# wifi_ring.net
KiCad netlist of a schematic drawn in EAGLE
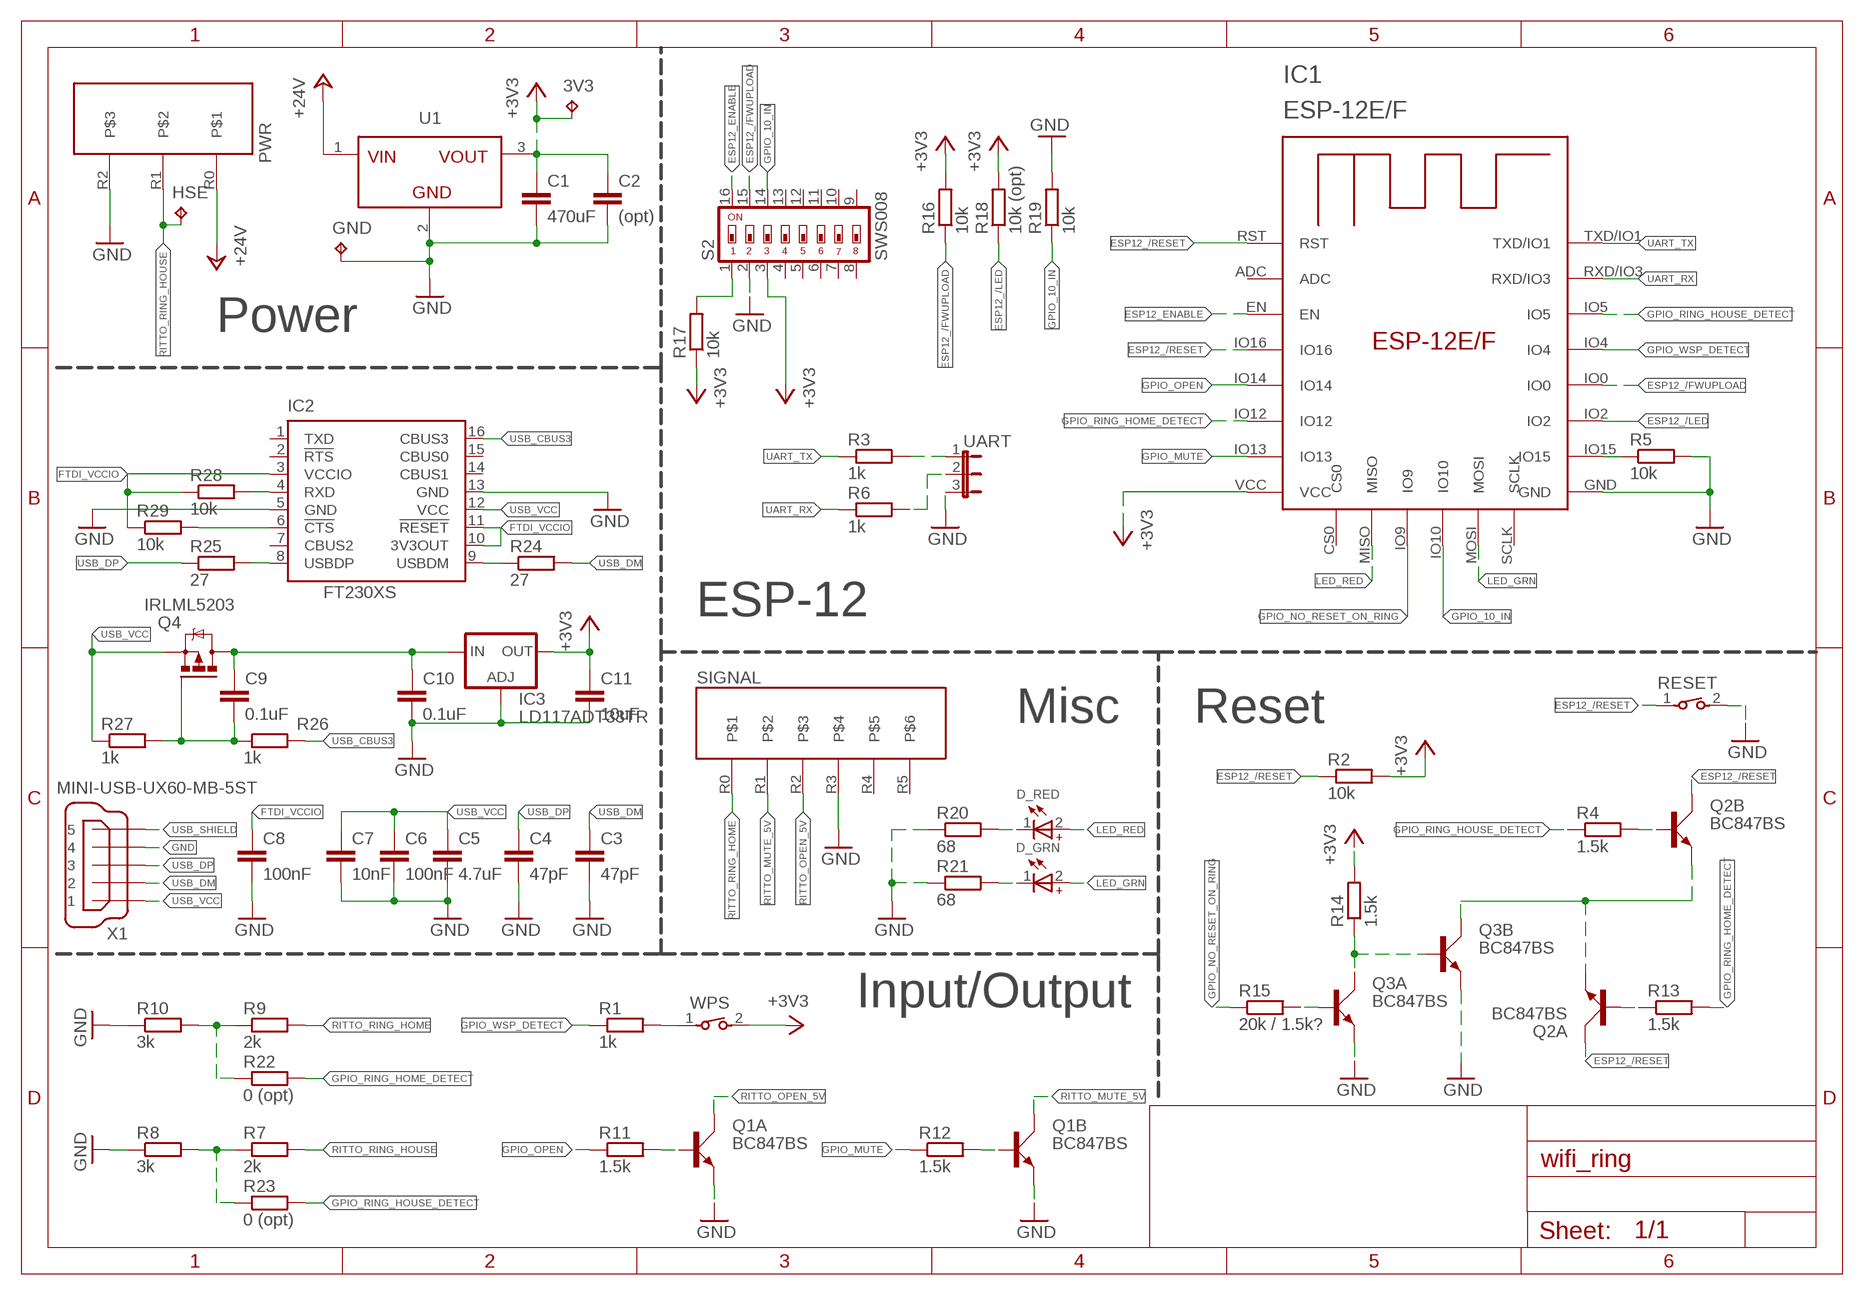
[diagram p0: schematic, sheet 1]

(export (version "E")
  (design (tool "Eeschema 10.0.6"))
  (components
    (comp (ref "3V3")
      (value "TPTP10SQ")
      (footprint "eagle-import:TP10SQ")
      (libsource (lib "eagle-import") (part "TPTP10SQ"))
    )
    (comp (ref "C1")
      (value "470uF")
      (footprint "eagle-import:C1206")
      (libsource (lib "eagle-import") (part "C-EUC1206"))
    )
    (comp (ref "C2")
      (value "(opt)")
      (footprint "eagle-import:C1206")
      (libsource (lib "eagle-import") (part "C-EUC1206"))
    )
    (comp (ref "C3")
      (value "47pF")
      (footprint "eagle-import:C1206")
      (libsource (lib "eagle-import") (part "C-EUC1206"))
    )
    (comp (ref "C4")
      (value "47pF")
      (footprint "eagle-import:C1206")
      (libsource (lib "eagle-import") (part "C-EUC1206"))
    )
    (comp (ref "C5")
      (value "4.7uF")
      (footprint "eagle-import:C1206")
      (libsource (lib "eagle-import") (part "C-EUC1206"))
    )
    (comp (ref "C6")
      (value "100nF")
      (footprint "eagle-import:C1206")
      (libsource (lib "eagle-import") (part "C-EUC1206"))
    )
    (comp (ref "C7")
      (value "10nF")
      (footprint "eagle-import:C1206")
      (libsource (lib "eagle-import") (part "C-EUC1206"))
    )
    (comp (ref "C8")
      (value "100nF")
      (footprint "eagle-import:C1206")
      (libsource (lib "eagle-import") (part "C-EUC1206"))
    )
    (comp (ref "C9")
      (value "0.1uF")
      (footprint "eagle-import:C1206")
      (libsource (lib "eagle-import") (part "C-EUC1206"))
    )
    (comp (ref "C10")
      (value "0.1uF")
      (footprint "eagle-import:C1206")
      (libsource (lib "eagle-import") (part "C-EUC1206"))
    )
    (comp (ref "C11")
      (value "10uF")
      (footprint "eagle-import:C1206")
      (libsource (lib "eagle-import") (part "C-EUC1206"))
    )
    (comp (ref "D_GRN")
      (value "WL-SMRW_1206_CYL_156120VS75300_NOR")
      (footprint "eagle-import:WL-SMRW_1206_CYL")
      (libsource (lib "eagle-import") (part "WL-SMRW_1206_CYL_NOR_156120VS75300"))
    )
    (comp (ref "D_RED")
      (value "WL-SMRW_1206_CYL_156120RS75300_NOR")
      (footprint "eagle-import:WL-SMRW_1206_CYL")
      (libsource (lib "eagle-import") (part "WL-SMRW_1206_CYL_NOR_156120RS75300"))
    )
    (comp (ref "GND")
      (value "TPTP10SQ")
      (footprint "eagle-import:TP10SQ")
      (libsource (lib "eagle-import") (part "TPTP10SQ"))
    )
    (comp (ref "HSE")
      (value "TPTP10SQ")
      (footprint "eagle-import:TP10SQ")
      (libsource (lib "eagle-import") (part "TPTP10SQ"))
    )
    (comp (ref "IC1")
      (value "ESP-12E/F")
      (footprint "eagle-import:ESP-12E")
      (libsource (lib "eagle-import") (part "ESP-12E/F"))
    )
    (comp (ref "IC2")
      (value "FT230XS")
      (footprint "eagle-import:SSOP16")
      (libsource (lib "eagle-import") (part "FT230XS"))
    )
    (comp (ref "IC3")
      (value "LD117ADT33TR")
      (footprint "eagle-import:DPACK")
      (libsource (lib "eagle-import") (part "LD117A?DT33TR"))
    )
    (comp (ref "PWR")
      (value "RAST_3")
      (footprint "eagle-import:RAST_3")
      (libsource (lib "eagle-import") (part "RAST_3"))
    )
    (comp (ref "Q1")
      (value "BC847BS")
      (footprint "eagle-import:SOT363_PHILIPS")
      (libsource (lib "eagle-import") (part "BC847BS"))
    )
    (comp (ref "Q2")
      (value "BC847BS")
      (footprint "eagle-import:SOT363_PHILIPS")
      (libsource (lib "eagle-import") (part "BC847BS"))
    )
    (comp (ref "Q3")
      (value "BC847BS")
      (footprint "eagle-import:SOT363_PHILIPS")
      (libsource (lib "eagle-import") (part "BC847BS"))
    )
    (comp (ref "Q4")
      (value "IRLML5203")
      (footprint "eagle-import:MICRO3")
      (libsource (lib "eagle-import") (part "IRLML5203"))
    )
    (comp (ref "R1")
      (value "1k")
      (footprint "eagle-import:R1206")
      (libsource (lib "eagle-import") (part "R-EU_R1206"))
    )
    (comp (ref "R2")
      (value "10k")
      (footprint "eagle-import:R1206")
      (libsource (lib "eagle-import") (part "R-EU_R1206"))
    )
    (comp (ref "R3")
      (value "1k")
      (footprint "eagle-import:R1206")
      (libsource (lib "eagle-import") (part "R-EU_R1206"))
    )
    (comp (ref "R4")
      (value "1.5k")
      (footprint "eagle-import:R1206")
      (libsource (lib "eagle-import") (part "R-EU_R1206"))
    )
    (comp (ref "R5")
      (value "10k")
      (footprint "eagle-import:R1206")
      (libsource (lib "eagle-import") (part "R-EU_R1206"))
    )
    (comp (ref "R6")
      (value "1k")
      (footprint "eagle-import:R1206")
      (libsource (lib "eagle-import") (part "R-EU_R1206"))
    )
    (comp (ref "R7")
      (value "2k")
      (footprint "eagle-import:R1206")
      (libsource (lib "eagle-import") (part "R-EU_R1206"))
    )
    (comp (ref "R8")
      (value "3k")
      (footprint "eagle-import:R1206")
      (libsource (lib "eagle-import") (part "R-EU_R1206"))
    )
    (comp (ref "R9")
      (value "2k")
      (footprint "eagle-import:R1206")
      (libsource (lib "eagle-import") (part "R-EU_R1206"))
    )
    (comp (ref "R10")
      (value "3k")
      (footprint "eagle-import:R1206")
      (libsource (lib "eagle-import") (part "R-EU_R1206"))
    )
    (comp (ref "R11")
      (value "1.5k")
      (footprint "eagle-import:R1206")
      (libsource (lib "eagle-import") (part "R-EU_R1206"))
    )
    (comp (ref "R12")
      (value "1.5k")
      (footprint "eagle-import:R1206")
      (libsource (lib "eagle-import") (part "R-EU_R1206"))
    )
    (comp (ref "R13")
      (value "1.5k")
      (footprint "eagle-import:R1206")
      (libsource (lib "eagle-import") (part "R-EU_R1206"))
    )
    (comp (ref "R14")
      (value "1.5k")
      (footprint "eagle-import:R1206")
      (libsource (lib "eagle-import") (part "R-EU_R1206"))
    )
    (comp (ref "R15")
      (value "20k / 1.5k?")
      (footprint "eagle-import:R1206")
      (libsource (lib "eagle-import") (part "R-EU_R1206"))
    )
    (comp (ref "R16")
      (value "10k")
      (footprint "eagle-import:R1206")
      (libsource (lib "eagle-import") (part "R-EU_R1206"))
    )
    (comp (ref "R17")
      (value "10k")
      (footprint "eagle-import:R1206")
      (libsource (lib "eagle-import") (part "R-EU_R1206"))
    )
    (comp (ref "R18")
      (value "10k (opt)")
      (footprint "eagle-import:R1206")
      (libsource (lib "eagle-import") (part "R-EU_R1206"))
    )
    (comp (ref "R19")
      (value "10k")
      (footprint "eagle-import:R1206")
      (libsource (lib "eagle-import") (part "R-EU_R1206"))
    )
    (comp (ref "R20")
      (value "68")
      (footprint "eagle-import:R1206")
      (libsource (lib "eagle-import") (part "R-EU_R1206"))
    )
    (comp (ref "R21")
      (value "68")
      (footprint "eagle-import:R1206")
      (libsource (lib "eagle-import") (part "R-EU_R1206"))
    )
    (comp (ref "R22")
      (value "0 (opt)")
      (footprint "eagle-import:R1206")
      (libsource (lib "eagle-import") (part "R-EU_R1206"))
    )
    (comp (ref "R23")
      (value "0 (opt)")
      (footprint "eagle-import:R1206")
      (libsource (lib "eagle-import") (part "R-EU_R1206"))
    )
    (comp (ref "R24")
      (value "27")
      (footprint "eagle-import:R1206")
      (libsource (lib "eagle-import") (part "R-EU_R1206"))
    )
    (comp (ref "R25")
      (value "27")
      (footprint "eagle-import:R1206")
      (libsource (lib "eagle-import") (part "R-EU_R1206"))
    )
    (comp (ref "R26")
      (value "1k")
      (footprint "eagle-import:R1206")
      (libsource (lib "eagle-import") (part "R-EU_R1206"))
    )
    (comp (ref "R27")
      (value "1k")
      (footprint "eagle-import:R1206")
      (libsource (lib "eagle-import") (part "R-EU_R1206"))
    )
    (comp (ref "R28")
      (value "10k")
      (footprint "eagle-import:R1206")
      (libsource (lib "eagle-import") (part "R-EU_R1206"))
    )
    (comp (ref "R29")
      (value "10k")
      (footprint "eagle-import:R1206")
      (libsource (lib "eagle-import") (part "R-EU_R1206"))
    )
    (comp (ref "RESET")
      (value "434123025816")
      (footprint "eagle-import:434123025816")
      (libsource (lib "eagle-import") (part "434123025816"))
    )
    (comp (ref "S2")
      (value "SWS008")
      (footprint "eagle-import:SMS-008")
      (libsource (lib "eagle-import") (part "SWS008"))
    )
    (comp (ref "SIGNAL")
      (value "RAST_6")
      (footprint "eagle-import:RAST_6")
      (libsource (lib "eagle-import") (part "RAST_6"))
    )
    (comp (ref "U1")
      (value "MAGI³C-FDSM_SIP-3_173950378_17395XX78")
      (footprint "eagle-import:MAGI³C-FDSM_17395XX78")
      (libsource (lib "eagle-import") (part "MAGI³C-FDSM_SIP-3_17395XX78_173950378"))
    )
    (comp (ref "UART")
      (value "JP2E")
      (footprint "eagle-import:JP2")
      (libsource (lib "eagle-import") (part "JP2E"))
    )
    (comp (ref "WPS")
      (value "434123025816")
      (footprint "eagle-import:434123025816")
      (libsource (lib "eagle-import") (part "434123025816"))
    )
    (comp (ref "X1")
      (value "MINI-USB-UX60-MB-5ST")
      (footprint "eagle-import:UX60-MB-5ST")
      (libsource (lib "eagle-import") (part "MINI-USB-UX60-MB-5ST"))
    )
  )
  (nets
    (net (code "1") (name "+3V3") (class "Default")
      (node (ref "3V3") (pin "TP") (pinfunction "TP_TP") (pintype "input"))
      (node (ref "C1") (pin "1") (pinfunction "1_1") (pintype "passive"))
      (node (ref "C11") (pin "1") (pinfunction "1_1") (pintype "passive"))
      (node (ref "C2") (pin "1") (pinfunction "1_1") (pintype "passive"))
      (node (ref "IC1") (pin "VCC") (pinfunction "VCC_VCC") (pintype "power_in"))
      (node (ref "IC3") (pin "4") (pinfunction "OUT_4") (pintype "passive"))
      (node (ref "R14") (pin "2") (pinfunction "2_2") (pintype "passive"))
      (node (ref "R16") (pin "2") (pinfunction "2_2") (pintype "passive"))
      (node (ref "R17") (pin "1") (pinfunction "1_1") (pintype "passive"))
      (node (ref "R18") (pin "2") (pinfunction "2_2") (pintype "passive"))
      (node (ref "R2") (pin "2") (pinfunction "2_2") (pintype "passive"))
      (node (ref "S2") (pin "3") (pinfunction "3_3") (pintype "passive"))
      (node (ref "U1") (pin "3") (pinfunction "VOUT_3") (pintype "output"))
      (node (ref "WPS") (pin "2") (pinfunction "2_2") (pintype "passive"))
    )
    (net (code "2") (name "+24V") (class "Default")
      (node (ref "PWR") (pin "R0") (pinfunction "P$1_R0") (pintype "passive"))
      (node (ref "U1") (pin "1") (pinfunction "VIN_1") (pintype "input"))
    )
    (net (code "3") (name "ESP12_ENABLE") (class "Default")
      (node (ref "IC1") (pin "EN") (pinfunction "EN_EN") (pintype "bidirectional"))
      (node (ref "S2") (pin "16") (pinfunction "16_16") (pintype "passive"))
    )
    (net (code "4") (name "ESP12_{slash}FWUPLOAD") (class "Default")
      (node (ref "IC1") (pin "IO0") (pinfunction "IO0_IO0") (pintype "bidirectional"))
      (node (ref "R16") (pin "1") (pinfunction "1_1") (pintype "passive"))
      (node (ref "S2") (pin "15") (pinfunction "15_15") (pintype "passive"))
    )
    (net (code "5") (name "ESP12_{slash}LED") (class "Default")
      (node (ref "IC1") (pin "IO2") (pinfunction "IO2_IO2") (pintype "bidirectional"))
      (node (ref "R18") (pin "1") (pinfunction "1_1") (pintype "passive"))
    )
    (net (code "6") (name "ESP12_{slash}RESET") (class "Default")
      (node (ref "IC1") (pin "IO16") (pinfunction "IO16_IO16") (pintype "bidirectional"))
      (node (ref "IC1") (pin "RST") (pinfunction "RST_RST") (pintype "input"))
      (node (ref "Q2") (pin "3") (pinfunction "C_3") (pintype "passive"))
      (node (ref "Q2") (pin "6") (pinfunction "C_6") (pintype "passive"))
      (node (ref "R2") (pin "1") (pinfunction "1_1") (pintype "passive"))
      (node (ref "RESET") (pin "1") (pinfunction "1_1") (pintype "passive"))
    )
    (net (code "7") (name "FTDI_VCCIO") (class "Default")
      (node (ref "C8") (pin "1") (pinfunction "1_1") (pintype "passive"))
      (node (ref "IC2") (pin "10") (pinfunction "3V3OUT_10") (pintype "output"))
      (node (ref "IC2") (pin "11") (pinfunction "~{RESET}_11") (pintype "input"))
      (node (ref "IC2") (pin "3") (pinfunction "VCCIO_3") (pintype "power_in"))
      (node (ref "R28") (pin "1") (pinfunction "1_1") (pintype "passive"))
      (node (ref "R29") (pin "1") (pinfunction "1_1") (pintype "passive"))
    )
    (net (code "8") (name "GND") (class "Default")
      (node (ref "C1") (pin "2") (pinfunction "2_2") (pintype "passive"))
      (node (ref "C10") (pin "2") (pinfunction "2_2") (pintype "passive"))
      (node (ref "C11") (pin "2") (pinfunction "2_2") (pintype "passive"))
      (node (ref "C2") (pin "2") (pinfunction "2_2") (pintype "passive"))
      (node (ref "C3") (pin "2") (pinfunction "2_2") (pintype "passive"))
      (node (ref "C4") (pin "2") (pinfunction "2_2") (pintype "passive"))
      (node (ref "C5") (pin "2") (pinfunction "2_2") (pintype "passive"))
      (node (ref "C6") (pin "2") (pinfunction "2_2") (pintype "passive"))
      (node (ref "C7") (pin "2") (pinfunction "2_2") (pintype "passive"))
      (node (ref "C8") (pin "2") (pinfunction "2_2") (pintype "passive"))
      (node (ref "GND") (pin "TP") (pinfunction "TP_TP") (pintype "input"))
      (node (ref "IC1") (pin "GND") (pinfunction "GND_GND") (pintype "power_in"))
      (node (ref "IC2") (pin "13") (pinfunction "GND_13") (pintype "power_in"))
      (node (ref "IC2") (pin "5") (pinfunction "GND_5") (pintype "power_in"))
      (node (ref "IC3") (pin "1") (pinfunction "ADJ_1") (pintype "input"))
      (node (ref "PWR") (pin "R2") (pinfunction "P$3_R2") (pintype "passive"))
      (node (ref "Q1") (pin "1") (pinfunction "E_1") (pintype "passive"))
      (node (ref "Q1") (pin "4") (pinfunction "E_4") (pintype "passive"))
      (node (ref "Q3") (pin "1") (pinfunction "E_1") (pintype "passive"))
      (node (ref "Q3") (pin "4") (pinfunction "E_4") (pintype "passive"))
      (node (ref "R10") (pin "1") (pinfunction "1_1") (pintype "passive"))
      (node (ref "R19") (pin "2") (pinfunction "2_2") (pintype "passive"))
      (node (ref "R20") (pin "1") (pinfunction "1_1") (pintype "passive"))
      (node (ref "R21") (pin "1") (pinfunction "1_1") (pintype "passive"))
      (node (ref "R5") (pin "2") (pinfunction "2_2") (pintype "passive"))
      (node (ref "R8") (pin "1") (pinfunction "1_1") (pintype "passive"))
      (node (ref "RESET") (pin "2") (pinfunction "2_2") (pintype "passive"))
      (node (ref "S2") (pin "2") (pinfunction "2_2") (pintype "passive"))
      (node (ref "SIGNAL") (pin "R3") (pinfunction "P$4_R3") (pintype "bidirectional"))
      (node (ref "U1") (pin "2") (pinfunction "GND_2") (pintype "passive"))
      (node (ref "UART") (pin "3") (pinfunction "3_3") (pintype "passive"))
      (node (ref "X1") (pin "4") (pinfunction "4_4") (pintype "input"))
    )
    (net (code "9") (name "GPIO_10_IN") (class "Default")
      (node (ref "IC1") (pin "IO10") (pinfunction "IO10_IO10") (pintype "bidirectional"))
      (node (ref "R19") (pin "1") (pinfunction "1_1") (pintype "passive"))
      (node (ref "S2") (pin "14") (pinfunction "14_14") (pintype "passive"))
    )
    (net (code "10") (name "GPIO_MUTE") (class "Default")
      (node (ref "IC1") (pin "IO13") (pinfunction "IO13_IO13") (pintype "bidirectional"))
      (node (ref "R12") (pin "1") (pinfunction "1_1") (pintype "passive"))
    )
    (net (code "11") (name "GPIO_NO_RESET_ON_RING") (class "Default")
      (node (ref "IC1") (pin "IO9") (pinfunction "IO9_IO9") (pintype "bidirectional"))
      (node (ref "R15") (pin "1") (pinfunction "1_1") (pintype "passive"))
    )
    (net (code "12") (name "GPIO_OPEN") (class "Default")
      (node (ref "IC1") (pin "IO14") (pinfunction "IO14_IO14") (pintype "bidirectional"))
      (node (ref "R11") (pin "1") (pinfunction "1_1") (pintype "passive"))
    )
    (net (code "13") (name "GPIO_RING_HOME_DETECT") (class "Default")
      (node (ref "IC1") (pin "IO12") (pinfunction "IO12_IO12") (pintype "bidirectional"))
      (node (ref "R13") (pin "2") (pinfunction "2_2") (pintype "passive"))
      (node (ref "R22") (pin "2") (pinfunction "2_2") (pintype "passive"))
    )
    (net (code "14") (name "GPIO_RING_HOUSE_DETECT") (class "Default")
      (node (ref "IC1") (pin "IO5") (pinfunction "IO5_IO5") (pintype "bidirectional"))
      (node (ref "R23") (pin "2") (pinfunction "2_2") (pintype "passive"))
      (node (ref "R4") (pin "1") (pinfunction "1_1") (pintype "passive"))
    )
    (net (code "15") (name "GPIO_WSP_DETECT") (class "Default")
      (node (ref "IC1") (pin "IO4") (pinfunction "IO4_IO4") (pintype "bidirectional"))
      (node (ref "R1") (pin "1") (pinfunction "1_1") (pintype "passive"))
    )
    (net (code "16") (name "LED_GRN") (class "Default")
      (node (ref "D_GRN") (pin "2") (pinfunction "+_2") (pintype "passive"))
      (node (ref "IC1") (pin "MOSI") (pinfunction "MOSI_MOSI") (pintype "bidirectional"))
    )
    (net (code "17") (name "LED_RED") (class "Default")
      (node (ref "D_RED") (pin "2") (pinfunction "+_2") (pintype "passive"))
      (node (ref "IC1") (pin "MISO") (pinfunction "MISO_MISO") (pintype "bidirectional"))
    )
    (net (code "18") (name "Net-(D_GRN--)") (class "Default")
      (node (ref "D_GRN") (pin "1") (pinfunction "-_1") (pintype "passive"))
      (node (ref "R21") (pin "2") (pinfunction "2_2") (pintype "passive"))
    )
    (net (code "19") (name "Net-(D_RED--)") (class "Default")
      (node (ref "D_RED") (pin "1") (pinfunction "-_1") (pintype "passive"))
      (node (ref "R20") (pin "2") (pinfunction "2_2") (pintype "passive"))
    )
    (net (code "20") (name "Net-(IC1-PadIO15)") (class "Default")
      (node (ref "IC1") (pin "IO15") (pinfunction "IO15_IO15") (pintype "bidirectional"))
      (node (ref "R5") (pin "1") (pinfunction "1_1") (pintype "passive"))
    )
    (net (code "21") (name "Net-(IC2-RXD)") (class "Default")
      (node (ref "IC2") (pin "4") (pinfunction "RXD_4") (pintype "input"))
      (node (ref "R28") (pin "2") (pinfunction "2_2") (pintype "passive"))
    )
    (net (code "22") (name "Net-(IC2-USBDM)") (class "Default")
      (node (ref "IC2") (pin "9") (pinfunction "USBDM_9") (pintype "input"))
      (node (ref "R24") (pin "1") (pinfunction "1_1") (pintype "passive"))
    )
    (net (code "23") (name "Net-(IC2-USBDP)") (class "Default")
      (node (ref "IC2") (pin "8") (pinfunction "USBDP_8") (pintype "input"))
      (node (ref "R25") (pin "2") (pinfunction "2_2") (pintype "passive"))
    )
    (net (code "24") (name "Net-(IC2-~{CTS})") (class "Default")
      (node (ref "IC2") (pin "6") (pinfunction "~{CTS}_6") (pintype "input"))
      (node (ref "R29") (pin "2") (pinfunction "2_2") (pintype "passive"))
    )
    (net (code "25") (name "Net-(IC3-IN)") (class "Default")
      (node (ref "C10") (pin "1") (pinfunction "1_1") (pintype "passive"))
      (node (ref "C9") (pin "1") (pinfunction "1_1") (pintype "passive"))
      (node (ref "IC3") (pin "3") (pinfunction "IN_3") (pintype "input"))
      (node (ref "Q4") (pin "3") (pinfunction "D_3") (pintype "passive"))
    )
    (net (code "26") (name "Net-(Q1A-B)") (class "Default")
      (node (ref "Q1") (pin "2") (pinfunction "B_2") (pintype "passive"))
      (node (ref "R11") (pin "2") (pinfunction "2_2") (pintype "passive"))
    )
    (net (code "27") (name "Net-(Q1B-B)") (class "Default")
      (node (ref "Q1") (pin "5") (pinfunction "B_5") (pintype "passive"))
      (node (ref "R12") (pin "2") (pinfunction "2_2") (pintype "passive"))
    )
    (net (code "28") (name "Net-(Q2A-B)") (class "Default")
      (node (ref "Q2") (pin "2") (pinfunction "B_2") (pintype "passive"))
      (node (ref "R13") (pin "1") (pinfunction "1_1") (pintype "passive"))
    )
    (net (code "29") (name "Net-(Q2A-E)") (class "Default")
      (node (ref "Q2") (pin "1") (pinfunction "E_1") (pintype "passive"))
      (node (ref "Q2") (pin "4") (pinfunction "E_4") (pintype "passive"))
      (node (ref "Q3") (pin "3") (pinfunction "C_3") (pintype "passive"))
    )
    (net (code "30") (name "Net-(Q2B-B)") (class "Default")
      (node (ref "Q2") (pin "5") (pinfunction "B_5") (pintype "passive"))
      (node (ref "R4") (pin "2") (pinfunction "2_2") (pintype "passive"))
    )
    (net (code "31") (name "Net-(Q3A-B)") (class "Default")
      (node (ref "Q3") (pin "2") (pinfunction "B_2") (pintype "passive"))
      (node (ref "R15") (pin "2") (pinfunction "2_2") (pintype "passive"))
    )
    (net (code "32") (name "Net-(Q3A-C)") (class "Default")
      (node (ref "Q3") (pin "5") (pinfunction "B_5") (pintype "passive"))
      (node (ref "Q3") (pin "6") (pinfunction "C_6") (pintype "passive"))
      (node (ref "R14") (pin "1") (pinfunction "1_1") (pintype "passive"))
    )
    (net (code "33") (name "Net-(Q4-G)") (class "Default")
      (node (ref "C9") (pin "2") (pinfunction "2_2") (pintype "passive"))
      (node (ref "Q4") (pin "1") (pinfunction "G_1") (pintype "passive"))
      (node (ref "R26") (pin "1") (pinfunction "1_1") (pintype "passive"))
      (node (ref "R27") (pin "2") (pinfunction "2_2") (pintype "passive"))
    )
    (net (code "34") (name "Net-(R1-Pad2)") (class "Default")
      (node (ref "R1") (pin "2") (pinfunction "2_2") (pintype "passive"))
      (node (ref "WPS") (pin "1") (pinfunction "1_1") (pintype "passive"))
    )
    (net (code "35") (name "Net-(R3-Pad2)") (class "Default")
      (node (ref "R3") (pin "2") (pinfunction "2_2") (pintype "passive"))
      (node (ref "UART") (pin "1") (pinfunction "1_1") (pintype "passive"))
    )
    (net (code "36") (name "Net-(R6-Pad2)") (class "Default")
      (node (ref "R6") (pin "2") (pinfunction "2_2") (pintype "passive"))
      (node (ref "UART") (pin "2") (pinfunction "2_2") (pintype "passive"))
    )
    (net (code "37") (name "Net-(R10-Pad2)") (class "Default")
      (node (ref "R10") (pin "2") (pinfunction "2_2") (pintype "passive"))
      (node (ref "R22") (pin "1") (pinfunction "1_1") (pintype "passive"))
      (node (ref "R9") (pin "1") (pinfunction "1_1") (pintype "passive"))
    )
    (net (code "38") (name "Net-(R17-Pad2)") (class "Default")
      (node (ref "R17") (pin "2") (pinfunction "2_2") (pintype "passive"))
      (node (ref "S2") (pin "1") (pinfunction "1_1") (pintype "passive"))
    )
    (net (code "39") (name "Net-(R23-Pad1)") (class "Default")
      (node (ref "R23") (pin "1") (pinfunction "1_1") (pintype "passive"))
      (node (ref "R7") (pin "1") (pinfunction "1_1") (pintype "passive"))
      (node (ref "R8") (pin "2") (pinfunction "2_2") (pintype "passive"))
    )
    (net (code "40") (name "RITTO_MUTE_5V") (class "Default")
      (node (ref "Q1") (pin "3") (pinfunction "C_3") (pintype "passive"))
      (node (ref "SIGNAL") (pin "R1") (pinfunction "P$2_R1") (pintype "bidirectional"))
    )
    (net (code "41") (name "RITTO_OPEN_5V") (class "Default")
      (node (ref "Q1") (pin "6") (pinfunction "C_6") (pintype "passive"))
      (node (ref "SIGNAL") (pin "R2") (pinfunction "P$3_R2") (pintype "bidirectional"))
    )
    (net (code "42") (name "RITTO_RING_HOME") (class "Default")
      (node (ref "R9") (pin "2") (pinfunction "2_2") (pintype "passive"))
      (node (ref "SIGNAL") (pin "R0") (pinfunction "P$1_R0") (pintype "bidirectional"))
    )
    (net (code "43") (name "RITTO_RING_HOUSE") (class "Default")
      (node (ref "HSE") (pin "TP") (pinfunction "TP_TP") (pintype "input"))
      (node (ref "PWR") (pin "R1") (pinfunction "P$2_R1") (pintype "passive"))
      (node (ref "R7") (pin "2") (pinfunction "2_2") (pintype "passive"))
    )
    (net (code "44") (name "UART_RX") (class "Default")
      (node (ref "IC1") (pin "RXD/IO3") (pinfunction "RXD/IO3_RXD/IO3") (pintype "bidirectional"))
      (node (ref "R6") (pin "1") (pinfunction "1_1") (pintype "passive"))
    )
    (net (code "45") (name "UART_TX") (class "Default")
      (node (ref "IC1") (pin "TXD/IO1") (pinfunction "TXD/IO1_TXD/IO1") (pintype "bidirectional"))
      (node (ref "R3") (pin "1") (pinfunction "1_1") (pintype "passive"))
    )
    (net (code "46") (name "USB_CBUS3") (class "Default")
      (node (ref "IC2") (pin "16") (pinfunction "CBUS3_16") (pintype "bidirectional"))
      (node (ref "R26") (pin "2") (pinfunction "2_2") (pintype "passive"))
    )
    (net (code "47") (name "USB_DM") (class "Default")
      (node (ref "C3") (pin "1") (pinfunction "1_1") (pintype "passive"))
      (node (ref "R24") (pin "2") (pinfunction "2_2") (pintype "passive"))
      (node (ref "X1") (pin "2") (pinfunction "2_2") (pintype "input"))
    )
    (net (code "48") (name "USB_DP") (class "Default")
      (node (ref "C4") (pin "1") (pinfunction "1_1") (pintype "passive"))
      (node (ref "R25") (pin "1") (pinfunction "1_1") (pintype "passive"))
      (node (ref "X1") (pin "3") (pinfunction "3_3") (pintype "input"))
    )
    (net (code "49") (name "USB_SHIELD") (class "Default")
      (node (ref "X1") (pin "5") (pinfunction "5_5") (pintype "input"))
    )
    (net (code "50") (name "USB_VCC") (class "Default")
      (node (ref "C5") (pin "1") (pinfunction "1_1") (pintype "passive"))
      (node (ref "C6") (pin "1") (pinfunction "1_1") (pintype "passive"))
      (node (ref "C7") (pin "1") (pinfunction "1_1") (pintype "passive"))
      (node (ref "IC2") (pin "12") (pinfunction "VCC_12") (pintype "power_in"))
      (node (ref "Q4") (pin "2") (pinfunction "S_2") (pintype "passive"))
      (node (ref "R27") (pin "1") (pinfunction "1_1") (pintype "passive"))
      (node (ref "X1") (pin "1") (pinfunction "1_1") (pintype "input"))
    )
    (net (code "51") (name "unconnected-(IC1-PadADC)") (class "Default")
      (node (ref "IC1") (pin "ADC") (pinfunction "ADC_ADC") (pintype "bidirectional"))
    )
    (net (code "52") (name "unconnected-(IC1-PadCS0)") (class "Default")
      (node (ref "IC1") (pin "CS0") (pinfunction "CS0_CS0") (pintype "bidirectional"))
    )
    (net (code "53") (name "unconnected-(IC1-PadSCLK)") (class "Default")
      (node (ref "IC1") (pin "SCLK") (pinfunction "SCLK_SCLK") (pintype "bidirectional"))
    )
    (net (code "54") (name "unconnected-(IC2-CBUS0-Pad15)") (class "Default")
      (node (ref "IC2") (pin "15") (pinfunction "CBUS0_15") (pintype "bidirectional"))
    )
    (net (code "55") (name "unconnected-(IC2-CBUS1-Pad14)") (class "Default")
      (node (ref "IC2") (pin "14") (pinfunction "CBUS1_14") (pintype "bidirectional"))
    )
    (net (code "56") (name "unconnected-(IC2-CBUS2-Pad7)") (class "Default")
      (node (ref "IC2") (pin "7") (pinfunction "CBUS2_7") (pintype "bidirectional"))
    )
    (net (code "57") (name "unconnected-(IC2-TXD-Pad1)") (class "Default")
      (node (ref "IC2") (pin "1") (pinfunction "TXD_1") (pintype "output"))
    )
    (net (code "58") (name "unconnected-(IC2-~{RTS}-Pad2)") (class "Default")
      (node (ref "IC2") (pin "2") (pinfunction "~{RTS}_2") (pintype "output"))
    )
    (net (code "59") (name "unconnected-(S2-Pad4)") (class "Default")
      (node (ref "S2") (pin "4") (pinfunction "4_4") (pintype "passive"))
    )
    (net (code "60") (name "unconnected-(S2-Pad5)") (class "Default")
      (node (ref "S2") (pin "5") (pinfunction "5_5") (pintype "passive"))
    )
    (net (code "61") (name "unconnected-(S2-Pad6)") (class "Default")
      (node (ref "S2") (pin "6") (pinfunction "6_6") (pintype "passive"))
    )
    (net (code "62") (name "unconnected-(S2-Pad7)") (class "Default")
      (node (ref "S2") (pin "7") (pinfunction "7_7") (pintype "passive"))
    )
    (net (code "63") (name "unconnected-(S2-Pad8)") (class "Default")
      (node (ref "S2") (pin "8") (pinfunction "8_8") (pintype "passive"))
    )
    (net (code "64") (name "unconnected-(S2-Pad9)") (class "Default")
      (node (ref "S2") (pin "9") (pinfunction "9_9") (pintype "passive"))
    )
    (net (code "65") (name "unconnected-(S2-Pad10)") (class "Default")
      (node (ref "S2") (pin "10") (pinfunction "10_10") (pintype "passive"))
    )
    (net (code "66") (name "unconnected-(S2-Pad11)") (class "Default")
      (node (ref "S2") (pin "11") (pinfunction "11_11") (pintype "passive"))
    )
    (net (code "67") (name "unconnected-(S2-Pad12)") (class "Default")
      (node (ref "S2") (pin "12") (pinfunction "12_12") (pintype "passive"))
    )
    (net (code "68") (name "unconnected-(S2-Pad13)") (class "Default")
      (node (ref "S2") (pin "13") (pinfunction "13_13") (pintype "passive"))
    )
    (net (code "69") (name "unconnected-(SIGNAL-P$5-PadR4)") (class "Default")
      (node (ref "SIGNAL") (pin "R4") (pinfunction "P$5_R4") (pintype "bidirectional"))
    )
    (net (code "70") (name "unconnected-(SIGNAL-P$6-PadR5)") (class "Default")
      (node (ref "SIGNAL") (pin "R5") (pinfunction "P$6_R5") (pintype "bidirectional"))
    )
  )
)
